# PixiFlood_1_9_PTH.net
KiCad netlist of a schematic drawn in EAGLE
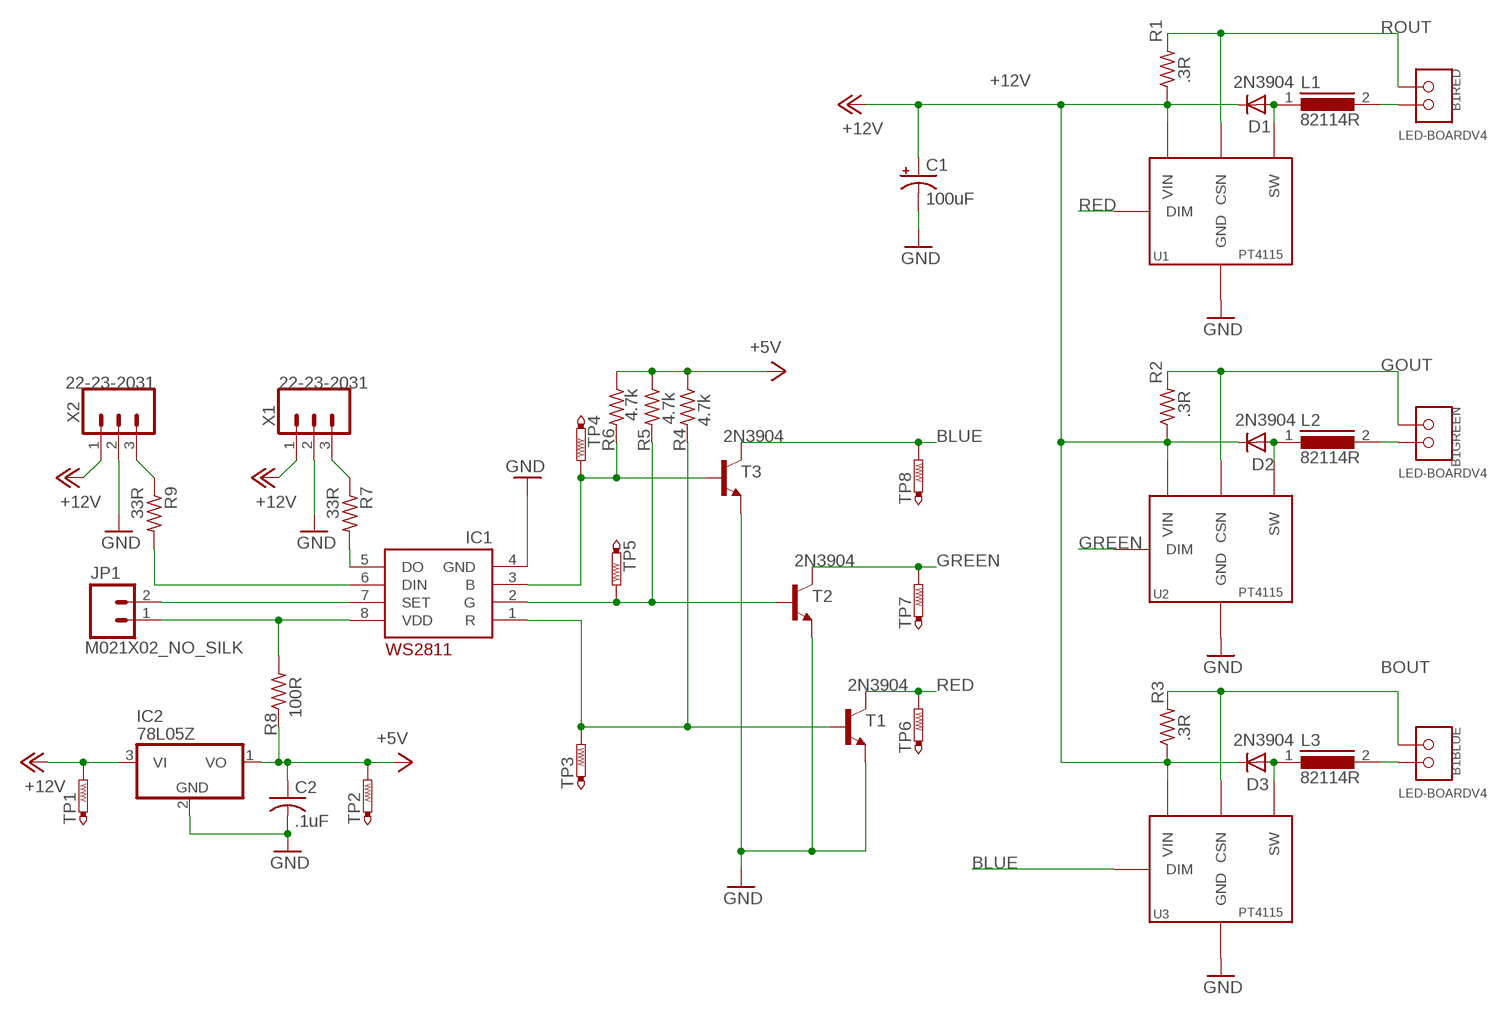
[diagram p0: schematic, sheet 1]

(export (version "E")
  (design (tool "Eeschema 10.0.6"))
  (components
    (comp (ref "B1")
      (value "LED-BOARDV4")
      (footprint "eagle-import:LED_BOARD-V4")
      (libsource (lib "eagle-import") (part "LED-BOARDV4"))
    )
    (comp (ref "C1")
      (value "100uF")
      (footprint "eagle-import:TT2D6L")
      (libsource (lib "eagle-import") (part "CPOL-USTT2D6L"))
    )
    (comp (ref "C2")
      (value ".1uF")
      (footprint "eagle-import:C050-024X044")
      (libsource (lib "eagle-import") (part "C-US050-024X044"))
    )
    (comp (ref "D1")
      (value "2N3904")
      (footprint "eagle-import:DO07")
      (libsource (lib "eagle-import") (part "DIODE-DO07"))
    )
    (comp (ref "D2")
      (value "2N3904")
      (footprint "eagle-import:DO07")
      (libsource (lib "eagle-import") (part "DIODE-DO07"))
    )
    (comp (ref "D3")
      (value "2N3904")
      (footprint "eagle-import:DO07")
      (libsource (lib "eagle-import") (part "DIODE-DO07"))
    )
    (comp (ref "IC1")
      (value "WS2811-SOP8")
      (footprint "eagle-import:SO08-SKINNYPADS")
      (libsource (lib "eagle-import") (part "WS2811-SOP8"))
    )
    (comp (ref "IC2")
      (value "78L05Z")
      (footprint "eagle-import:TO92")
      (libsource (lib "eagle-import") (part "78ZL05"))
    )
    (comp (ref "JP1")
      (value "M021X02_NO_SILK")
      (footprint "eagle-import:1X02_NO_SILK")
      (libsource (lib "eagle-import") (part "M021X02_NO_SILK"))
    )
    (comp (ref "L1")
      (value "82114R")
      (footprint "eagle-import:82114R")
      (libsource (lib "eagle-import") (part "82114R"))
    )
    (comp (ref "L2")
      (value "82114R")
      (footprint "eagle-import:82114R")
      (libsource (lib "eagle-import") (part "82114R"))
    )
    (comp (ref "L3")
      (value "82114R")
      (footprint "eagle-import:82114R")
      (libsource (lib "eagle-import") (part "82114R"))
    )
    (comp (ref "R1")
      (value ".3R")
      (footprint "eagle-import:0204_7")
      (libsource (lib "eagle-import") (part "resistor_R-US_0204/7"))
    )
    (comp (ref "R2")
      (value ".3R")
      (footprint "eagle-import:0204_7")
      (libsource (lib "eagle-import") (part "resistor_R-US_0204/7"))
    )
    (comp (ref "R3")
      (value ".3R")
      (footprint "eagle-import:0204_7")
      (libsource (lib "eagle-import") (part "resistor_R-US_0204/7"))
    )
    (comp (ref "R4")
      (value "4.7k")
      (footprint "eagle-import:0204_7")
      (libsource (lib "eagle-import") (part "resistor_R-US_0204/7"))
    )
    (comp (ref "R5")
      (value "4.7k")
      (footprint "eagle-import:0204_7")
      (libsource (lib "eagle-import") (part "resistor_R-US_0204/7"))
    )
    (comp (ref "R6")
      (value "4.7k")
      (footprint "eagle-import:0204_7")
      (libsource (lib "eagle-import") (part "resistor_R-US_0204/7"))
    )
    (comp (ref "R7")
      (value "33R")
      (footprint "eagle-import:0204_7")
      (libsource (lib "eagle-import") (part "R-US_0204/7"))
    )
    (comp (ref "R8")
      (value "100R")
      (footprint "eagle-import:0204_7")
      (libsource (lib "eagle-import") (part "R-US_0204/7"))
    )
    (comp (ref "R9")
      (value "33R")
      (footprint "eagle-import:0204_7")
      (libsource (lib "eagle-import") (part "R-US_0204/7"))
    )
    (comp (ref "T1")
      (value "2N3904")
      (footprint "eagle-import:TO92")
      (libsource (lib "eagle-import") (part "2N3904"))
    )
    (comp (ref "T2")
      (value "2N3904")
      (footprint "eagle-import:TO92")
      (libsource (lib "eagle-import") (part "2N3904"))
    )
    (comp (ref "T3")
      (value "2N3904")
      (footprint "eagle-import:TO92")
      (libsource (lib "eagle-import") (part "2N3904"))
    )
    (comp (ref "TP1")
      (value "PTR1B2,54")
      (footprint "eagle-import:B2,54")
      (libsource (lib "eagle-import") (part "PTR1B2,54"))
    )
    (comp (ref "TP2")
      (value "PTR1B2,54")
      (footprint "eagle-import:B2,54")
      (libsource (lib "eagle-import") (part "PTR1B2,54"))
    )
    (comp (ref "TP3")
      (value "PTR1B1,27")
      (footprint "eagle-import:B1,27")
      (libsource (lib "eagle-import") (part "PTR1B1,27"))
    )
    (comp (ref "TP4")
      (value "PTR1B1,27")
      (footprint "eagle-import:B1,27")
      (libsource (lib "eagle-import") (part "PTR1B1,27"))
    )
    (comp (ref "TP5")
      (value "PTR1B1,27")
      (footprint "eagle-import:B1,27")
      (libsource (lib "eagle-import") (part "PTR1B1,27"))
    )
    (comp (ref "TP6")
      (value "PTR1B1,27")
      (footprint "eagle-import:B1,27")
      (libsource (lib "eagle-import") (part "PTR1B1,27"))
    )
    (comp (ref "TP7")
      (value "PTR1B1,27")
      (footprint "eagle-import:B1,27")
      (libsource (lib "eagle-import") (part "PTR1B1,27"))
    )
    (comp (ref "TP8")
      (value "PTR1B1,27")
      (footprint "eagle-import:B1,27")
      (libsource (lib "eagle-import") (part "PTR1B1,27"))
    )
    (comp (ref "U1")
      (value "PT4115B89E-A2")
      (footprint "eagle-import:SOT89-5-A")
      (libsource (lib "eagle-import") (part "PT4115B89E-A2"))
    )
    (comp (ref "U2")
      (value "PT4115B89E-A2")
      (footprint "eagle-import:SOT89-5-A")
      (libsource (lib "eagle-import") (part "PT4115B89E-A2"))
    )
    (comp (ref "U3")
      (value "PT4115B89E-A2")
      (footprint "eagle-import:SOT89-5-A")
      (libsource (lib "eagle-import") (part "PT4115B89E-A2"))
    )
    (comp (ref "X1")
      (value "22-23-2031")
      (footprint "eagle-import:22-23-2031")
      (fields (field (name "MF") "MOLEX"))
      (libsource (lib "eagle-import") (part "22-23-2031"))
    )
    (comp (ref "X2")
      (value "22-23-2031")
      (footprint "eagle-import:22-23-2031")
      (fields (field (name "MF") "MOLEX"))
      (libsource (lib "eagle-import") (part "22-23-2031"))
    )
  )
  (nets
    (net (code "1") (name "+5V") (class "Default")
      (node (ref "C2") (pin "1") (pinfunction "1_1") (pintype "passive"))
      (node (ref "IC2") (pin "1") (pinfunction "VO_1") (pintype "passive"))
      (node (ref "R4") (pin "1") (pinfunction "1_1") (pintype "passive"))
      (node (ref "R5") (pin "1") (pinfunction "1_1") (pintype "passive"))
      (node (ref "R6") (pin "1") (pinfunction "1_1") (pintype "passive"))
      (node (ref "R8") (pin "1") (pinfunction "1_1") (pintype "passive"))
      (node (ref "TP2") (pin "TP") (pinfunction "TP_TP") (pintype "input"))
    )
    (net (code "2") (name "+12V") (class "Default")
      (node (ref "C1") (pin "+") (pinfunction "+_+") (pintype "passive"))
      (node (ref "D1") (pin "C") (pinfunction "C_C") (pintype "passive"))
      (node (ref "D2") (pin "C") (pinfunction "C_C") (pintype "passive"))
      (node (ref "D3") (pin "C") (pinfunction "C_C") (pintype "passive"))
      (node (ref "IC2") (pin "3") (pinfunction "VI_3") (pintype "input"))
      (node (ref "R1") (pin "1") (pinfunction "1_1") (pintype "passive"))
      (node (ref "R2") (pin "1") (pinfunction "1_1") (pintype "passive"))
      (node (ref "R3") (pin "1") (pinfunction "1_1") (pintype "passive"))
      (node (ref "TP1") (pin "TP") (pinfunction "TP_TP") (pintype "input"))
      (node (ref "U1") (pin "5") (pinfunction "VIN_5") (pintype "power_in"))
      (node (ref "U2") (pin "5") (pinfunction "VIN_5") (pintype "power_in"))
      (node (ref "U3") (pin "5") (pinfunction "VIN_5") (pintype "power_in"))
      (node (ref "X1") (pin "1") (pinfunction "1_1") (pintype "passive"))
      (node (ref "X2") (pin "1") (pinfunction "1_1") (pintype "passive"))
    )
    (net (code "3") (name "/BLUE") (class "Default")
      (node (ref "T3") (pin "1") (pinfunction "C_1") (pintype "passive"))
      (node (ref "TP8") (pin "TP") (pinfunction "TP_TP") (pintype "input"))
      (node (ref "U3") (pin "3") (pinfunction "DIM_3") (pintype "bidirectional"))
    )
    (net (code "4") (name "/BOUT") (class "Default")
      (node (ref "B1") (pin "B+") (pinfunction "P$2_B+") (pintype "bidirectional"))
      (node (ref "B1") (pin "B+@2") (pinfunction "P$2_B+@2") (pintype "bidirectional"))
      (node (ref "R3") (pin "2") (pinfunction "2_2") (pintype "passive"))
      (node (ref "U3") (pin "4") (pinfunction "CSN_4") (pintype "bidirectional"))
    )
    (net (code "5") (name "/GOUT") (class "Default")
      (node (ref "B1") (pin "G+") (pinfunction "P$2_G+") (pintype "bidirectional"))
      (node (ref "B1") (pin "G+@1") (pinfunction "P$2_G+@1") (pintype "bidirectional"))
      (node (ref "R2") (pin "2") (pinfunction "2_2") (pintype "passive"))
      (node (ref "U2") (pin "4") (pinfunction "CSN_4") (pintype "bidirectional"))
    )
    (net (code "6") (name "/GREEN") (class "Default")
      (node (ref "T2") (pin "1") (pinfunction "C_1") (pintype "passive"))
      (node (ref "TP7") (pin "TP") (pinfunction "TP_TP") (pintype "input"))
      (node (ref "U2") (pin "3") (pinfunction "DIM_3") (pintype "bidirectional"))
    )
    (net (code "7") (name "/RED") (class "Default")
      (node (ref "T1") (pin "1") (pinfunction "C_1") (pintype "passive"))
      (node (ref "TP6") (pin "TP") (pinfunction "TP_TP") (pintype "input"))
      (node (ref "U1") (pin "3") (pinfunction "DIM_3") (pintype "bidirectional"))
    )
    (net (code "8") (name "/ROUT") (class "Default")
      (node (ref "B1") (pin "R+") (pinfunction "P$2_R+") (pintype "bidirectional"))
      (node (ref "B1") (pin "R+@1") (pinfunction "P$2_R+@1") (pintype "bidirectional"))
      (node (ref "R1") (pin "2") (pinfunction "2_2") (pintype "passive"))
      (node (ref "U1") (pin "4") (pinfunction "CSN_4") (pintype "bidirectional"))
    )
    (net (code "9") (name "GND") (class "Default")
      (node (ref "C1") (pin "-") (pinfunction "-_-") (pintype "passive"))
      (node (ref "C2") (pin "2") (pinfunction "2_2") (pintype "passive"))
      (node (ref "IC1") (pin "4") (pinfunction "GND_4") (pintype "power_in"))
      (node (ref "IC2") (pin "2") (pinfunction "GND_2") (pintype "passive"))
      (node (ref "T1") (pin "3") (pinfunction "E_3") (pintype "passive"))
      (node (ref "T2") (pin "3") (pinfunction "E_3") (pintype "passive"))
      (node (ref "T3") (pin "3") (pinfunction "E_3") (pintype "passive"))
      (node (ref "U1") (pin "2") (pinfunction "GND_2") (pintype "power_in"))
      (node (ref "U1") (pin "2@1") (pinfunction "GND_2@1") (pintype "power_in"))
      (node (ref "U1") (pin "2@2") (pinfunction "GND_2@2") (pintype "power_in"))
      (node (ref "U1") (pin "2@3") (pinfunction "GND_2@3") (pintype "power_in"))
      (node (ref "U2") (pin "2") (pinfunction "GND_2") (pintype "power_in"))
      (node (ref "U2") (pin "2@1") (pinfunction "GND_2@1") (pintype "power_in"))
      (node (ref "U2") (pin "2@2") (pinfunction "GND_2@2") (pintype "power_in"))
      (node (ref "U2") (pin "2@3") (pinfunction "GND_2@3") (pintype "power_in"))
      (node (ref "U3") (pin "2") (pinfunction "GND_2") (pintype "power_in"))
      (node (ref "U3") (pin "2@1") (pinfunction "GND_2@1") (pintype "power_in"))
      (node (ref "U3") (pin "2@2") (pinfunction "GND_2@2") (pintype "power_in"))
      (node (ref "U3") (pin "2@3") (pinfunction "GND_2@3") (pintype "power_in"))
      (node (ref "X1") (pin "2") (pinfunction "2_2") (pintype "passive"))
      (node (ref "X2") (pin "2") (pinfunction "2_2") (pintype "passive"))
    )
    (net (code "10") (name "Net-(B1A-P$1-PadB-)") (class "Default")
      (node (ref "B1") (pin "B-") (pinfunction "P$1_B-") (pintype "bidirectional"))
      (node (ref "B1") (pin "B-@1") (pinfunction "P$1_B-@1") (pintype "bidirectional"))
      (node (ref "L3") (pin "2") (pinfunction "2_2") (pintype "passive"))
    )
    (net (code "11") (name "Net-(B1B-P$1-PadG-)") (class "Default")
      (node (ref "B1") (pin "G-") (pinfunction "P$1_G-") (pintype "bidirectional"))
      (node (ref "B1") (pin "G-@1") (pinfunction "P$1_G-@1") (pintype "bidirectional"))
      (node (ref "L2") (pin "2") (pinfunction "2_2") (pintype "passive"))
    )
    (net (code "12") (name "Net-(B1C-P$1-PadR-)") (class "Default")
      (node (ref "B1") (pin "R-") (pinfunction "P$1_R-") (pintype "bidirectional"))
      (node (ref "B1") (pin "R-@1") (pinfunction "P$1_R-@1") (pintype "bidirectional"))
      (node (ref "L1") (pin "2") (pinfunction "2_2") (pintype "passive"))
    )
    (net (code "13") (name "Net-(IC1-B)") (class "Default")
      (node (ref "IC1") (pin "3") (pinfunction "B_3") (pintype "open_collector"))
      (node (ref "R6") (pin "2") (pinfunction "2_2") (pintype "passive"))
      (node (ref "T3") (pin "2") (pinfunction "B_2") (pintype "passive"))
      (node (ref "TP4") (pin "TP") (pinfunction "TP_TP") (pintype "input"))
    )
    (net (code "14") (name "Net-(IC1-DIN)") (class "Default")
      (node (ref "IC1") (pin "6") (pinfunction "DIN_6") (pintype "input"))
      (node (ref "R9") (pin "2") (pinfunction "2_2") (pintype "passive"))
    )
    (net (code "15") (name "Net-(IC1-DO)") (class "Default")
      (node (ref "IC1") (pin "5") (pinfunction "DO_5") (pintype "output"))
      (node (ref "R7") (pin "2") (pinfunction "2_2") (pintype "passive"))
    )
    (net (code "16") (name "Net-(IC1-G)") (class "Default")
      (node (ref "IC1") (pin "2") (pinfunction "G_2") (pintype "open_collector"))
      (node (ref "R5") (pin "2") (pinfunction "2_2") (pintype "passive"))
      (node (ref "T2") (pin "2") (pinfunction "B_2") (pintype "passive"))
      (node (ref "TP5") (pin "TP") (pinfunction "TP_TP") (pintype "input"))
    )
    (net (code "17") (name "Net-(IC1-R)") (class "Default")
      (node (ref "IC1") (pin "1") (pinfunction "R_1") (pintype "open_collector"))
      (node (ref "R4") (pin "2") (pinfunction "2_2") (pintype "passive"))
      (node (ref "T1") (pin "2") (pinfunction "B_2") (pintype "passive"))
      (node (ref "TP3") (pin "TP") (pinfunction "TP_TP") (pintype "input"))
    )
    (net (code "18") (name "Net-(IC1-SET)") (class "Default")
      (node (ref "IC1") (pin "7") (pinfunction "SET_7") (pintype "input"))
      (node (ref "JP1") (pin "2") (pinfunction "2_2") (pintype "passive"))
    )
    (net (code "19") (name "Net-(IC1-VDD)") (class "Default")
      (node (ref "IC1") (pin "8") (pinfunction "VDD_8") (pintype "power_in"))
      (node (ref "JP1") (pin "1") (pinfunction "1_1") (pintype "passive"))
      (node (ref "R8") (pin "2") (pinfunction "2_2") (pintype "passive"))
    )
    (net (code "20") (name "Net-(R7-Pad1)") (class "Default")
      (node (ref "R7") (pin "1") (pinfunction "1_1") (pintype "passive"))
      (node (ref "X1") (pin "3") (pinfunction "3_3") (pintype "passive"))
    )
    (net (code "21") (name "Net-(R9-Pad1)") (class "Default")
      (node (ref "R9") (pin "1") (pinfunction "1_1") (pintype "passive"))
      (node (ref "X2") (pin "3") (pinfunction "3_3") (pintype "passive"))
    )
    (net (code "22") (name "Net-(U1-SW)") (class "Default")
      (node (ref "D1") (pin "A") (pinfunction "A_A") (pintype "passive"))
      (node (ref "L1") (pin "1") (pinfunction "1_1") (pintype "passive"))
      (node (ref "U1") (pin "1") (pinfunction "SW_1") (pintype "bidirectional"))
    )
    (net (code "23") (name "Net-(U2-SW)") (class "Default")
      (node (ref "D2") (pin "A") (pinfunction "A_A") (pintype "passive"))
      (node (ref "L2") (pin "1") (pinfunction "1_1") (pintype "passive"))
      (node (ref "U2") (pin "1") (pinfunction "SW_1") (pintype "bidirectional"))
    )
    (net (code "24") (name "Net-(U3-SW)") (class "Default")
      (node (ref "D3") (pin "A") (pinfunction "A_A") (pintype "passive"))
      (node (ref "L3") (pin "1") (pinfunction "1_1") (pintype "passive"))
      (node (ref "U3") (pin "1") (pinfunction "SW_1") (pintype "bidirectional"))
    )
  )
)
